# UV_Pneumatics_H-bridge.net
KiCad netlist of a schematic drawn in EAGLE
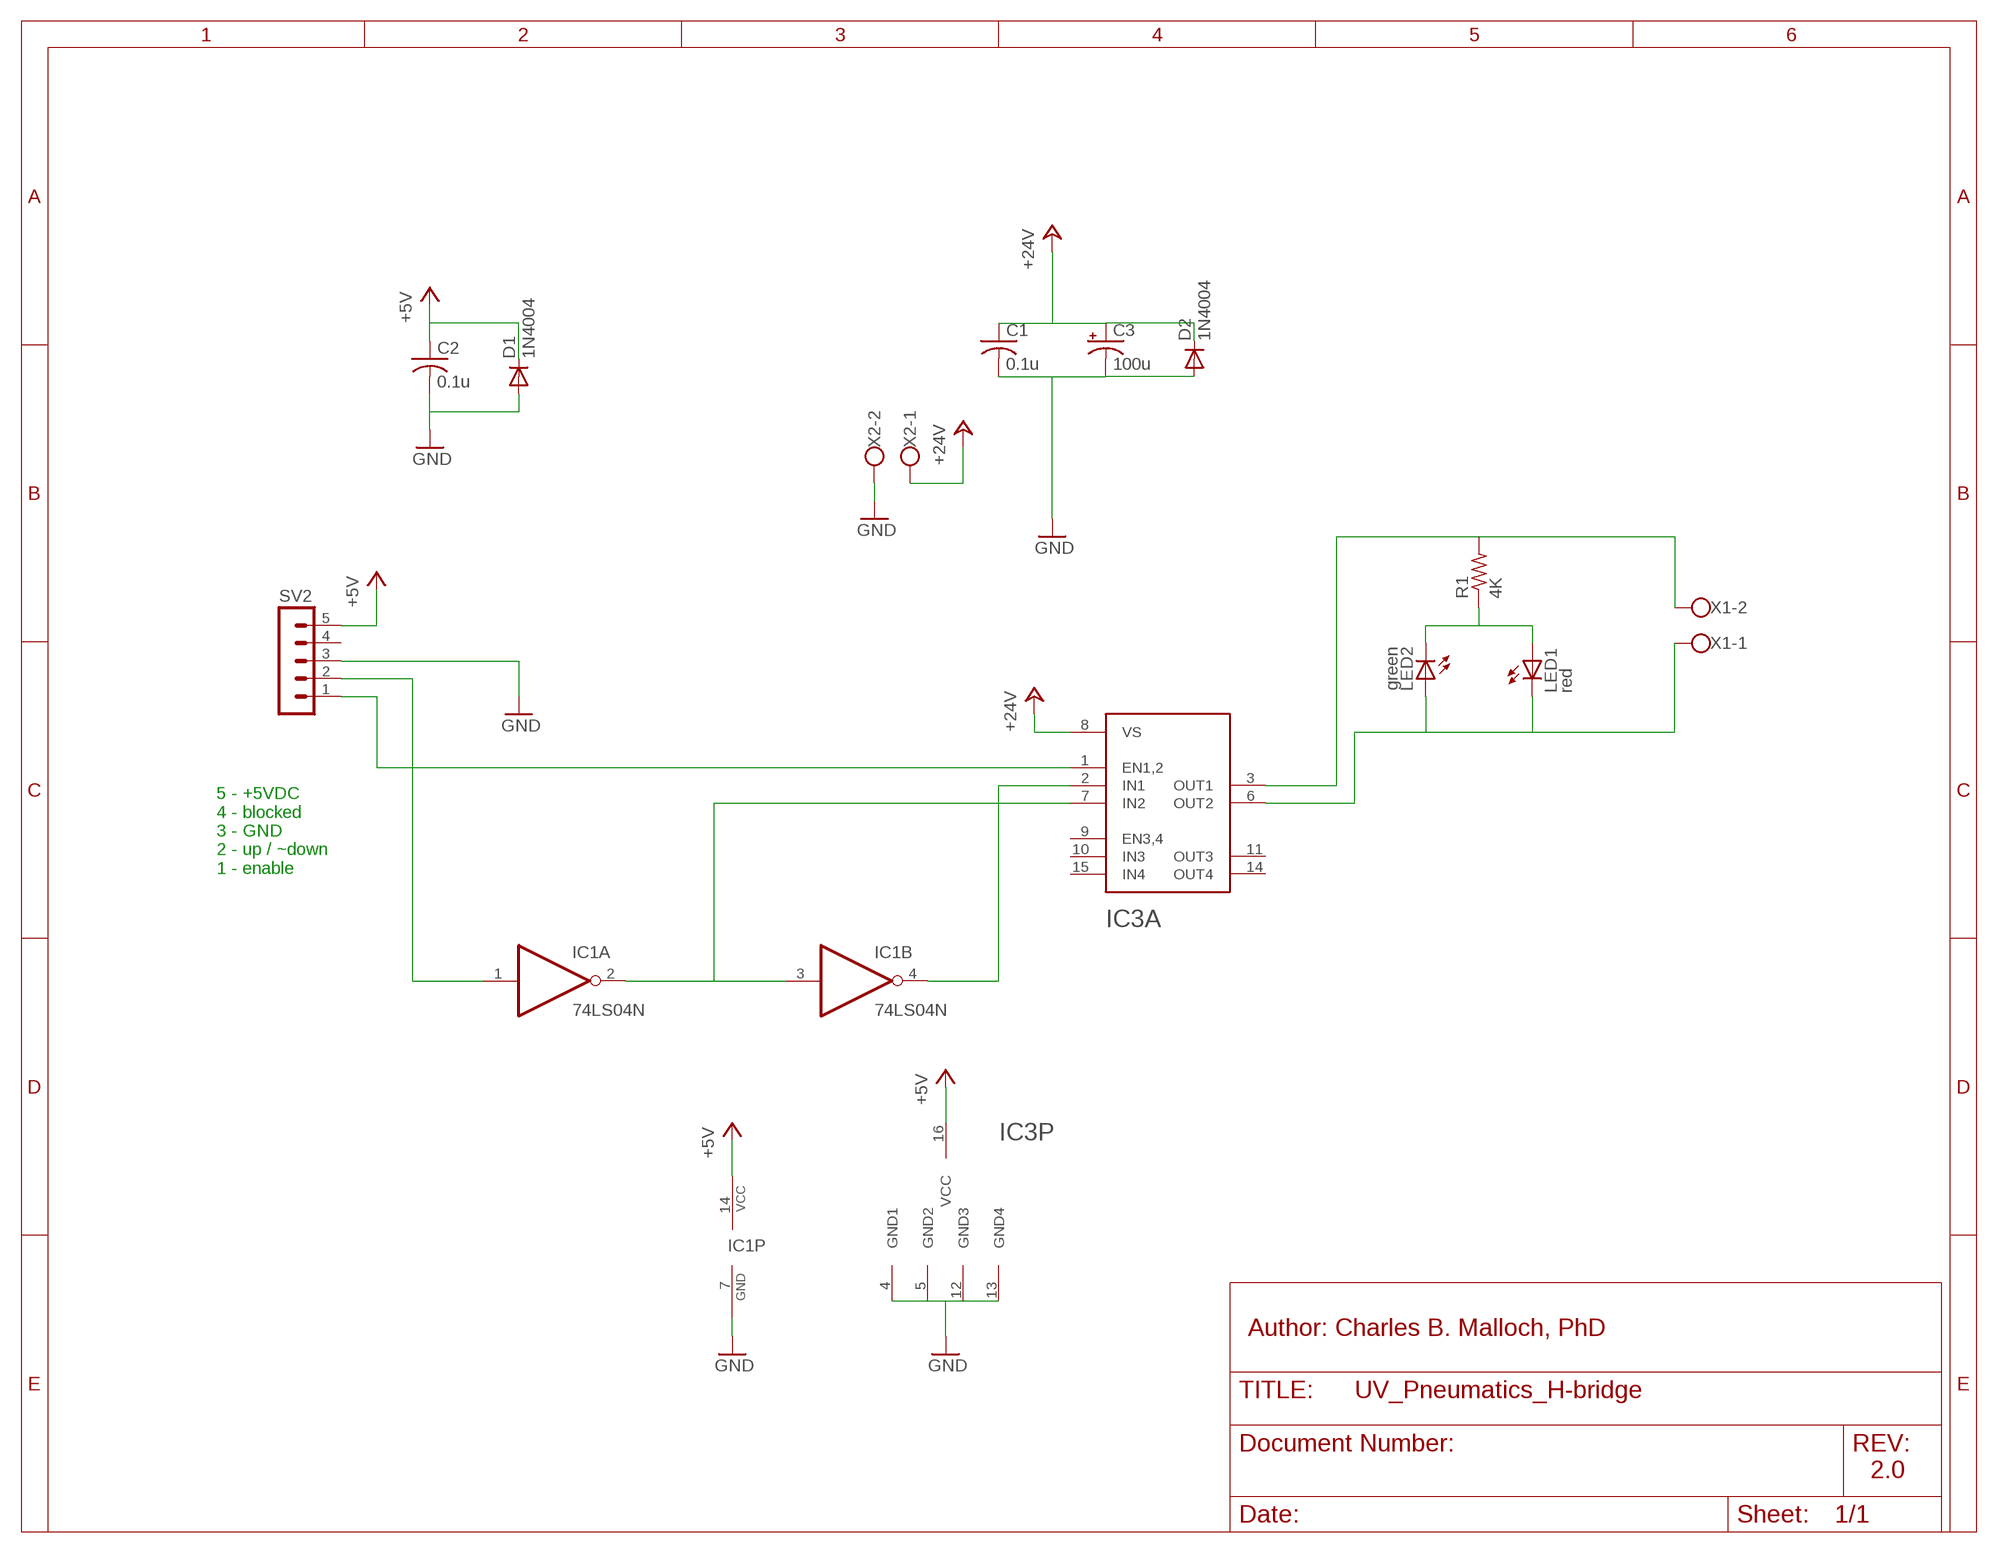
[diagram p0: schematic, sheet 1]

(export (version "E")
  (design (tool "Eeschema 10.0.6"))
  (components
    (comp (ref "C1")
      (value "0.1u")
      (footprint "eagle-import:C025-025X050")
      (libsource (lib "eagle-import") (part "C-US025-025X050"))
    )
    (comp (ref "C2")
      (value "0.1u")
      (footprint "eagle-import:C025-025X050")
      (libsource (lib "eagle-import") (part "C-US025-025X050"))
    )
    (comp (ref "C3")
      (value "100u")
      (footprint "eagle-import:E3,5-10")
      (libsource (lib "eagle-import") (part "CPOL-USE3.5-10"))
    )
    (comp (ref "D1")
      (value "1N4004")
      (footprint "eagle-import:DO41-10")
      (libsource (lib "eagle-import") (part "1N4004"))
    )
    (comp (ref "D2")
      (value "1N4004")
      (footprint "eagle-import:DO41-10")
      (libsource (lib "eagle-import") (part "1N4004"))
    )
    (comp (ref "IC1")
      (value "74LS04N")
      (footprint "eagle-import:DIL14")
      (libsource (lib "eagle-import") (part "7404NLS"))
    )
    (comp (ref "IC3")
      (value "L293D")
      (footprint "eagle-import:DIP16")
      (libsource (lib "eagle-import") (part "L293D"))
    )
    (comp (ref "LED1")
      (value "red")
      (footprint "eagle-import:LED3MM")
      (libsource (lib "eagle-import") (part "LED3MM"))
    )
    (comp (ref "LED2")
      (value "green")
      (footprint "eagle-import:LED3MM")
      (libsource (lib "eagle-import") (part "LED3MM"))
    )
    (comp (ref "R1")
      (value "4K")
      (footprint "eagle-import:0207_10")
      (libsource (lib "eagle-import") (part "R-US_0207/10"))
    )
    (comp (ref "SV2")
      (value "MA05-1")
      (footprint "eagle-import:MA05-1")
      (libsource (lib "eagle-import") (part "MA05-1"))
    )
    (comp (ref "X1")
      (value "W237-102")
      (footprint "eagle-import:W237-102")
      (fields (field (name "MPN") "237-102"))
      (libsource (lib "eagle-import") (part "W237-102"))
    )
    (comp (ref "X2")
      (value "W237-102")
      (footprint "eagle-import:W237-102")
      (fields (field (name "MPN") "237-102"))
      (libsource (lib "eagle-import") (part "W237-102"))
    )
  )
  (nets
    (net (code "1") (name "+5V") (class "Default")
      (node (ref "C2") (pin "1") (pinfunction "1_1") (pintype "passive"))
      (node (ref "D1") (pin "C") (pinfunction "C_C") (pintype "passive"))
      (node (ref "IC1") (pin "14") (pinfunction "VCC_14") (pintype "power_in"))
      (node (ref "IC3") (pin "16") (pinfunction "VCC_16") (pintype "power_in"))
      (node (ref "SV2") (pin "5") (pinfunction "5_5") (pintype "passive"))
    )
    (net (code "2") (name "+24V") (class "Default")
      (node (ref "C1") (pin "1") (pinfunction "1_1") (pintype "passive"))
      (node (ref "C3") (pin "+") (pinfunction "+_+") (pintype "passive"))
      (node (ref "D2") (pin "C") (pinfunction "C_C") (pintype "passive"))
      (node (ref "IC3") (pin "8") (pinfunction "VS_8") (pintype "power_in"))
      (node (ref "X2") (pin "1") (pinfunction "KL_1") (pintype "passive"))
    )
    (net (code "3") (name "GND") (class "Default")
      (node (ref "C1") (pin "2") (pinfunction "2_2") (pintype "passive"))
      (node (ref "C2") (pin "2") (pinfunction "2_2") (pintype "passive"))
      (node (ref "C3") (pin "-") (pinfunction "-_-") (pintype "passive"))
      (node (ref "D1") (pin "A") (pinfunction "A_A") (pintype "passive"))
      (node (ref "D2") (pin "A") (pinfunction "A_A") (pintype "passive"))
      (node (ref "IC1") (pin "7") (pinfunction "GND_7") (pintype "power_in"))
      (node (ref "IC3") (pin "12") (pinfunction "GND3_12") (pintype "power_in"))
      (node (ref "IC3") (pin "13") (pinfunction "GND4_13") (pintype "power_in"))
      (node (ref "IC3") (pin "4") (pinfunction "GND1_4") (pintype "power_in"))
      (node (ref "IC3") (pin "5") (pinfunction "GND2_5") (pintype "power_in"))
      (node (ref "SV2") (pin "3") (pinfunction "3_3") (pintype "passive"))
      (node (ref "X2") (pin "2") (pinfunction "KL_2") (pintype "passive"))
    )
    (net (code "4") (name "Net-(IC1A-I)") (class "Default")
      (node (ref "IC1") (pin "1") (pinfunction "I_1") (pintype "input"))
      (node (ref "SV2") (pin "2") (pinfunction "2_2") (pintype "passive"))
    )
    (net (code "5") (name "Net-(IC1A-O)") (class "Default")
      (node (ref "IC1") (pin "2") (pinfunction "O_2") (pintype "output"))
      (node (ref "IC1") (pin "3") (pinfunction "I_3") (pintype "input"))
      (node (ref "IC3") (pin "7") (pinfunction "IN2_7") (pintype "input"))
    )
    (net (code "6") (name "Net-(IC1B-O)") (class "Default")
      (node (ref "IC1") (pin "4") (pinfunction "O_4") (pintype "output"))
      (node (ref "IC3") (pin "2") (pinfunction "IN1_2") (pintype "input"))
    )
    (net (code "7") (name "Net-(IC3A-EN1,2)") (class "Default")
      (node (ref "IC3") (pin "1") (pinfunction "EN1,2_1") (pintype "input"))
      (node (ref "SV2") (pin "1") (pinfunction "1_1") (pintype "passive"))
    )
    (net (code "8") (name "Net-(IC3A-OUT1)") (class "Default")
      (node (ref "IC3") (pin "3") (pinfunction "OUT1_3") (pintype "output"))
      (node (ref "R1") (pin "2") (pinfunction "2_2") (pintype "passive"))
      (node (ref "X1") (pin "2") (pinfunction "KL_2") (pintype "passive"))
    )
    (net (code "9") (name "Net-(IC3A-OUT2)") (class "Default")
      (node (ref "IC3") (pin "6") (pinfunction "OUT2_6") (pintype "output"))
      (node (ref "LED1") (pin "K") (pinfunction "C_K") (pintype "passive"))
      (node (ref "LED2") (pin "A") (pinfunction "A_A") (pintype "passive"))
      (node (ref "X1") (pin "1") (pinfunction "KL_1") (pintype "passive"))
    )
    (net (code "10") (name "Net-(LED2-C)") (class "Default")
      (node (ref "LED1") (pin "A") (pinfunction "A_A") (pintype "passive"))
      (node (ref "LED2") (pin "K") (pinfunction "C_K") (pintype "passive"))
      (node (ref "R1") (pin "1") (pinfunction "1_1") (pintype "passive"))
    )
    (net (code "11") (name "unconnected-(IC3A-EN3,4-Pad9)") (class "Default")
      (node (ref "IC3") (pin "9") (pinfunction "EN3,4_9") (pintype "input"))
    )
    (net (code "12") (name "unconnected-(IC3A-IN3-Pad10)") (class "Default")
      (node (ref "IC3") (pin "10") (pinfunction "IN3_10") (pintype "input"))
    )
    (net (code "13") (name "unconnected-(IC3A-IN4-Pad15)") (class "Default")
      (node (ref "IC3") (pin "15") (pinfunction "IN4_15") (pintype "input"))
    )
    (net (code "14") (name "unconnected-(IC3A-OUT3-Pad11)") (class "Default")
      (node (ref "IC3") (pin "11") (pinfunction "OUT3_11") (pintype "output"))
    )
    (net (code "15") (name "unconnected-(IC3A-OUT4-Pad14)") (class "Default")
      (node (ref "IC3") (pin "14") (pinfunction "OUT4_14") (pintype "output"))
    )
    (net (code "16") (name "unconnected-(SV2-Pad4)") (class "Default")
      (node (ref "SV2") (pin "4") (pinfunction "4_4") (pintype "passive"))
    )
  )
)
